# APP_UD_red_588.net
KiCad netlist of a schematic drawn in EAGLE
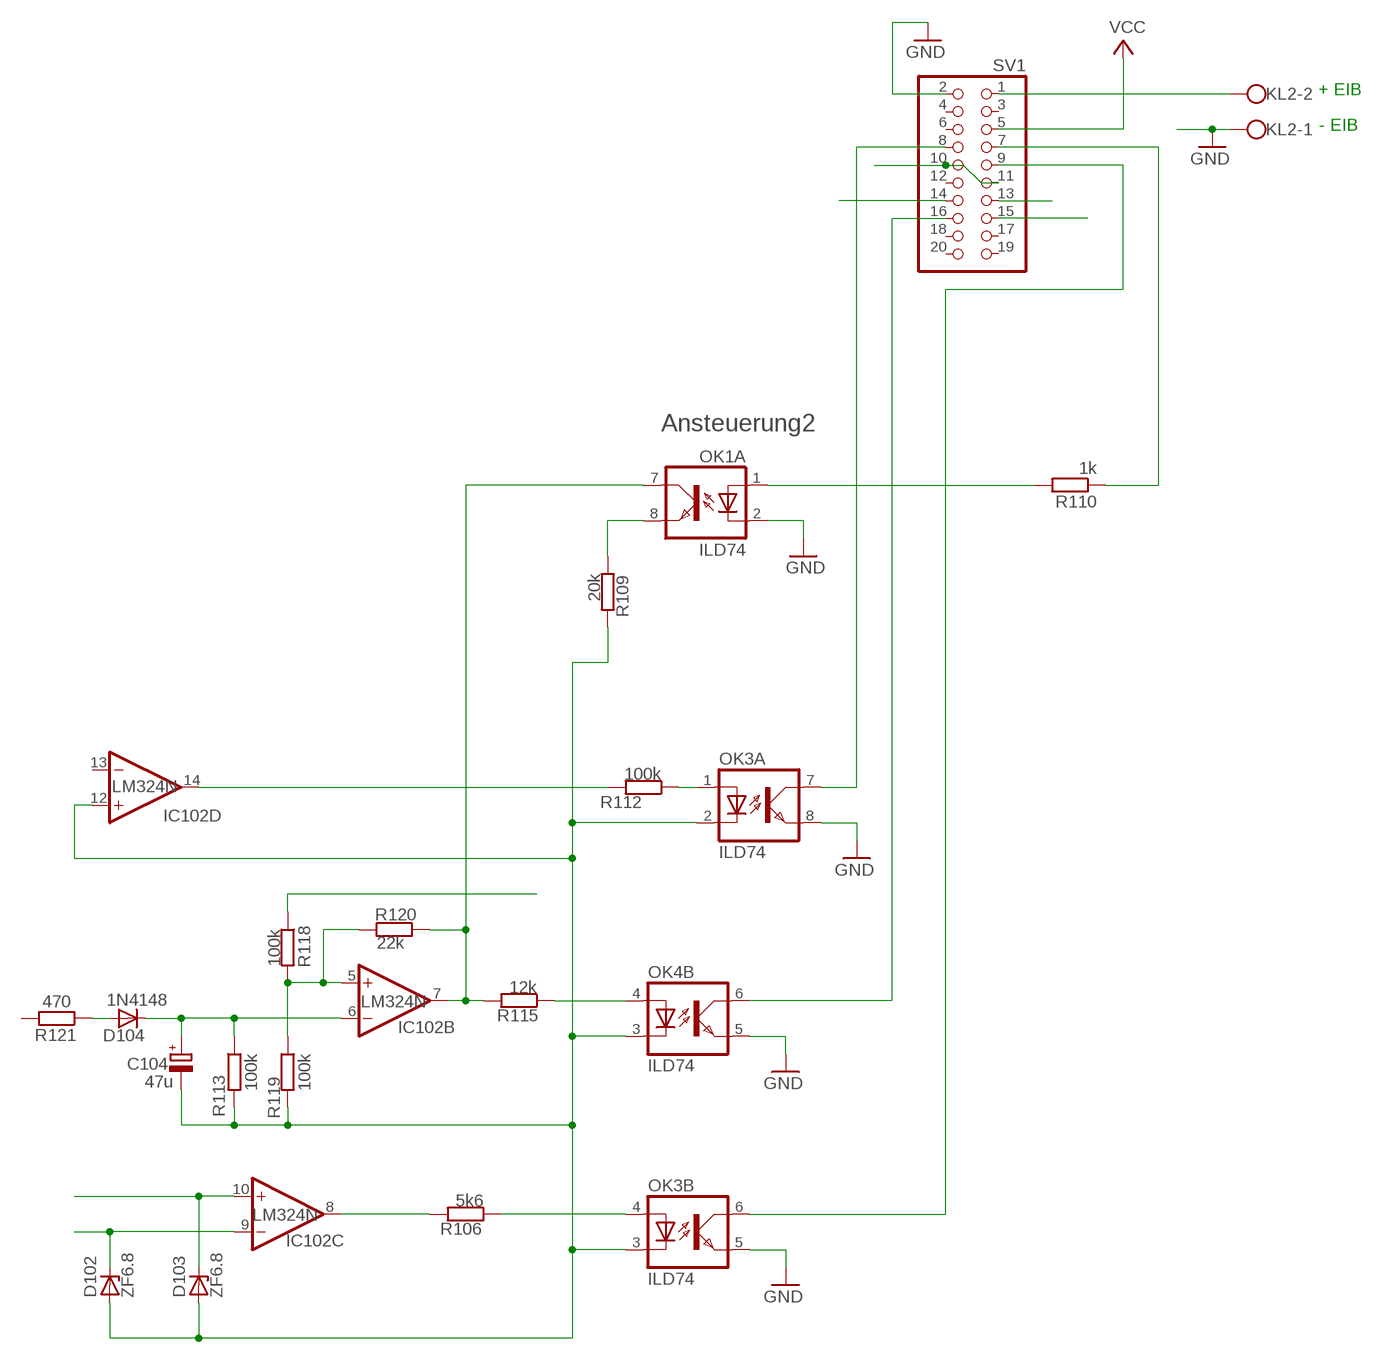
[diagram p0: schematic, sheet 1]

(export (version "E")
  (design (tool "Eeschema 10.0.6"))
  (components
    (comp (ref "C104")
      (value "47u")
      (footprint "eagle-import:E2-5")
      (libsource (lib "eagle-import") (part "CPOL-EUE2-5"))
    )
    (comp (ref "D102")
      (value "ZF6.8")
      (footprint "eagle-import:ZDIO-5")
      (libsource (lib "eagle-import") (part "ZENER-DIODEZD-5"))
    )
    (comp (ref "D103")
      (value "ZF6.8")
      (footprint "eagle-import:ZDIO-7.5")
      (libsource (lib "eagle-import") (part "ZENER-DIODEZD-7.5"))
    )
    (comp (ref "D104")
      (value "1N4148")
      (footprint "eagle-import:D-7")
      (libsource (lib "eagle-import") (part "1N4148DO35-7S"))
    )
    (comp (ref "IC102")
      (value "LM324N")
      (footprint "eagle-import:DIL14")
      (libsource (lib "eagle-import") (part "LM324N"))
    )
    (comp (ref "KL2")
      (value "W237-102")
      (footprint "eagle-import:W237-102")
      (libsource (lib "eagle-import") (part "W237-102"))
    )
    (comp (ref "OK1")
      (value "ILD74")
      (footprint "eagle-import:DIL08")
      (libsource (lib "eagle-import") (part "ILD2"))
    )
    (comp (ref "OK3")
      (value "ILD74")
      (footprint "eagle-import:DIL08")
      (libsource (lib "eagle-import") (part "ILD2"))
    )
    (comp (ref "OK4")
      (value "ILD74")
      (footprint "eagle-import:DIL08")
      (libsource (lib "eagle-import") (part "ILD2"))
    )
    (comp (ref "R106")
      (value "5k6")
      (footprint "eagle-import:0204_7")
      (libsource (lib "eagle-import") (part "R-EU_0204/7"))
    )
    (comp (ref "R109")
      (value "20k")
      (footprint "eagle-import:0204_7")
      (libsource (lib "eagle-import") (part "R-EU_0204/7"))
    )
    (comp (ref "R110")
      (value "1k")
      (footprint "eagle-import:0204_7")
      (libsource (lib "eagle-import") (part "R-EU_0204/7"))
    )
    (comp (ref "R112")
      (value "100k")
      (footprint "eagle-import:0207_15")
      (libsource (lib "eagle-import") (part "R-EU_0207/15"))
    )
    (comp (ref "R113")
      (value "100k")
      (footprint "eagle-import:0204_7")
      (libsource (lib "eagle-import") (part "R-EU_0204/7"))
    )
    (comp (ref "R115")
      (value "12k")
      (footprint "eagle-import:0204_7")
      (libsource (lib "eagle-import") (part "R-EU_0204/7"))
    )
    (comp (ref "R118")
      (value "100k")
      (footprint "eagle-import:0204_7")
      (libsource (lib "eagle-import") (part "R-EU_0204/7"))
    )
    (comp (ref "R119")
      (value "100k")
      (footprint "eagle-import:0204_7")
      (libsource (lib "eagle-import") (part "R-EU_0204/7"))
    )
    (comp (ref "R120")
      (value "22k")
      (footprint "eagle-import:0204_7")
      (libsource (lib "eagle-import") (part "R-EU_0204/7"))
    )
    (comp (ref "R121")
      (value "470")
      (footprint "eagle-import:0204_7")
      (libsource (lib "eagle-import") (part "R-EU_0204/7"))
    )
    (comp (ref "SV1")
      (value "PINHD-2X10")
      (footprint "eagle-import:2X10")
      (libsource (lib "eagle-import") (part "PINHD-2X10"))
    )
  )
  (nets
    (net (code "1") (name "GND") (class "Default")
      (node (ref "KL2") (pin "1") (pinfunction "KL_1") (pintype "passive"))
      (node (ref "OK1") (pin "2") (pinfunction "C_2") (pintype "passive"))
      (node (ref "OK3") (pin "5") (pinfunction "EMIT_5") (pintype "passive"))
      (node (ref "OK3") (pin "8") (pinfunction "EMIT_8") (pintype "passive"))
      (node (ref "OK4") (pin "5") (pinfunction "EMIT_5") (pintype "passive"))
      (node (ref "SV1") (pin "2") (pinfunction "2_2") (pintype "passive"))
    )
    (net (code "2") (name "Net-(D104-PadA)") (class "Default")
      (node (ref "D104") (pin "A") (pinfunction "A_A") (pintype "passive"))
      (node (ref "R121") (pin "1") (pinfunction "1_1") (pintype "passive"))
    )
    (net (code "3") (name "Net-(IC102B-+IN)") (class "Default")
      (node (ref "IC102") (pin "5") (pinfunction "+IN_5") (pintype "input"))
      (node (ref "R118") (pin "2") (pinfunction "2_2") (pintype "passive"))
      (node (ref "R119") (pin "1") (pinfunction "1_1") (pintype "passive"))
      (node (ref "R120") (pin "1") (pinfunction "1_1") (pintype "passive"))
    )
    (net (code "4") (name "Net-(IC102B--IN)") (class "Default")
      (node (ref "C104") (pin "+") (pinfunction "+_+") (pintype "passive"))
      (node (ref "D104") (pin "C") (pinfunction "C_C") (pintype "passive"))
      (node (ref "IC102") (pin "6") (pinfunction "-IN_6") (pintype "input"))
      (node (ref "R113") (pin "1") (pinfunction "1_1") (pintype "passive"))
    )
    (net (code "5") (name "Net-(IC102B-OUT)") (class "Default")
      (node (ref "IC102") (pin "7") (pinfunction "OUT_7") (pintype "output"))
      (node (ref "OK1") (pin "7") (pinfunction "COL_7") (pintype "passive"))
      (node (ref "R115") (pin "2") (pinfunction "2_2") (pintype "passive"))
      (node (ref "R120") (pin "2") (pinfunction "2_2") (pintype "passive"))
    )
    (net (code "6") (name "Net-(IC102C-+IN)") (class "Default")
      (node (ref "D103") (pin "C") (pinfunction "C_C") (pintype "passive"))
      (node (ref "IC102") (pin "10") (pinfunction "+IN_10") (pintype "input"))
    )
    (net (code "7") (name "Net-(IC102C--IN)") (class "Default")
      (node (ref "D102") (pin "C") (pinfunction "C_C") (pintype "passive"))
      (node (ref "IC102") (pin "9") (pinfunction "-IN_9") (pintype "input"))
    )
    (net (code "8") (name "Net-(IC102C-OUT)") (class "Default")
      (node (ref "IC102") (pin "8") (pinfunction "OUT_8") (pintype "output"))
      (node (ref "R106") (pin "2") (pinfunction "2_2") (pintype "passive"))
    )
    (net (code "9") (name "Net-(IC102D-+IN)") (class "Default")
      (node (ref "C104") (pin "-") (pinfunction "-_-") (pintype "passive"))
      (node (ref "D102") (pin "A") (pinfunction "A_A") (pintype "passive"))
      (node (ref "D103") (pin "A") (pinfunction "A_A") (pintype "passive"))
      (node (ref "IC102") (pin "12") (pinfunction "+IN_12") (pintype "input"))
      (node (ref "OK3") (pin "2") (pinfunction "C_2") (pintype "passive"))
      (node (ref "OK3") (pin "3") (pinfunction "C_3") (pintype "passive"))
      (node (ref "OK4") (pin "3") (pinfunction "C_3") (pintype "passive"))
      (node (ref "R109") (pin "2") (pinfunction "2_2") (pintype "passive"))
      (node (ref "R113") (pin "2") (pinfunction "2_2") (pintype "passive"))
      (node (ref "R119") (pin "2") (pinfunction "2_2") (pintype "passive"))
    )
    (net (code "10") (name "Net-(IC102D-OUT)") (class "Default")
      (node (ref "IC102") (pin "14") (pinfunction "OUT_14") (pintype "output"))
      (node (ref "R112") (pin "2") (pinfunction "2_2") (pintype "passive"))
    )
    (net (code "11") (name "Net-(KL2B-KL)") (class "Default")
      (node (ref "KL2") (pin "2") (pinfunction "KL_2") (pintype "passive"))
      (node (ref "SV1") (pin "1") (pinfunction "1_1") (pintype "passive"))
    )
    (net (code "12") (name "Net-(OK1A-A)") (class "Default")
      (node (ref "OK1") (pin "1") (pinfunction "A_1") (pintype "passive"))
      (node (ref "R110") (pin "2") (pinfunction "2_2") (pintype "passive"))
    )
    (net (code "13") (name "Net-(OK1A-EMIT)") (class "Default")
      (node (ref "OK1") (pin "8") (pinfunction "EMIT_8") (pintype "passive"))
      (node (ref "R109") (pin "1") (pinfunction "1_1") (pintype "passive"))
    )
    (net (code "14") (name "Net-(OK3A-A)") (class "Default")
      (node (ref "OK3") (pin "1") (pinfunction "A_1") (pintype "passive"))
      (node (ref "R112") (pin "1") (pinfunction "1_1") (pintype "passive"))
    )
    (net (code "15") (name "Net-(OK3A-COL)") (class "Default")
      (node (ref "OK3") (pin "7") (pinfunction "COL_7") (pintype "passive"))
      (node (ref "SV1") (pin "8") (pinfunction "8_8") (pintype "passive"))
    )
    (net (code "16") (name "Net-(OK3B-A)") (class "Default")
      (node (ref "OK3") (pin "4") (pinfunction "A_4") (pintype "passive"))
      (node (ref "R106") (pin "1") (pinfunction "1_1") (pintype "passive"))
    )
    (net (code "17") (name "Net-(OK3B-COL)") (class "Default")
      (node (ref "OK3") (pin "6") (pinfunction "COL_6") (pintype "passive"))
      (node (ref "SV1") (pin "9") (pinfunction "9_9") (pintype "passive"))
    )
    (net (code "18") (name "Net-(OK4B-A)") (class "Default")
      (node (ref "OK4") (pin "4") (pinfunction "A_4") (pintype "passive"))
      (node (ref "R115") (pin "1") (pinfunction "1_1") (pintype "passive"))
    )
    (net (code "19") (name "Net-(OK4B-COL)") (class "Default")
      (node (ref "OK4") (pin "6") (pinfunction "COL_6") (pintype "passive"))
      (node (ref "SV1") (pin "16") (pinfunction "16_16") (pintype "passive"))
    )
    (net (code "20") (name "Net-(R110-Pad1)") (class "Default")
      (node (ref "R110") (pin "1") (pinfunction "1_1") (pintype "passive"))
      (node (ref "SV1") (pin "7") (pinfunction "7_7") (pintype "passive"))
    )
    (net (code "21") (name "Net-(SV1-Pad10)") (class "Default")
      (node (ref "SV1") (pin "10") (pinfunction "10_10") (pintype "passive"))
      (node (ref "SV1") (pin "11") (pinfunction "11_11") (pintype "passive"))
    )
    (net (code "22") (name "VCC") (class "Default")
      (node (ref "SV1") (pin "5") (pinfunction "5_5") (pintype "passive"))
    )
    (net (code "23") (name "unconnected-(IC102D--IN-Pad13)") (class "Default")
      (node (ref "IC102") (pin "13") (pinfunction "-IN_13") (pintype "input"))
    )
    (net (code "24") (name "unconnected-(R118-Pad1)") (class "Default")
      (node (ref "R118") (pin "1") (pinfunction "1_1") (pintype "passive"))
    )
    (net (code "25") (name "unconnected-(R121-Pad2)") (class "Default")
      (node (ref "R121") (pin "2") (pinfunction "2_2") (pintype "passive"))
    )
    (net (code "26") (name "unconnected-(SV1-Pad3)") (class "Default")
      (node (ref "SV1") (pin "3") (pinfunction "3_3") (pintype "passive"))
    )
    (net (code "27") (name "unconnected-(SV1-Pad4)") (class "Default")
      (node (ref "SV1") (pin "4") (pinfunction "4_4") (pintype "passive"))
    )
    (net (code "28") (name "unconnected-(SV1-Pad6)") (class "Default")
      (node (ref "SV1") (pin "6") (pinfunction "6_6") (pintype "passive"))
    )
    (net (code "29") (name "unconnected-(SV1-Pad12)") (class "Default")
      (node (ref "SV1") (pin "12") (pinfunction "12_12") (pintype "passive"))
    )
    (net (code "30") (name "unconnected-(SV1-Pad13)") (class "Default")
      (node (ref "SV1") (pin "13") (pinfunction "13_13") (pintype "passive"))
    )
    (net (code "31") (name "unconnected-(SV1-Pad14)") (class "Default")
      (node (ref "SV1") (pin "14") (pinfunction "14_14") (pintype "passive"))
    )
    (net (code "32") (name "unconnected-(SV1-Pad15)") (class "Default")
      (node (ref "SV1") (pin "15") (pinfunction "15_15") (pintype "passive"))
    )
    (net (code "33") (name "unconnected-(SV1-Pad17)") (class "Default")
      (node (ref "SV1") (pin "17") (pinfunction "17_17") (pintype "passive"))
    )
    (net (code "34") (name "unconnected-(SV1-Pad18)") (class "Default")
      (node (ref "SV1") (pin "18") (pinfunction "18_18") (pintype "passive"))
    )
    (net (code "35") (name "unconnected-(SV1-Pad19)") (class "Default")
      (node (ref "SV1") (pin "19") (pinfunction "19_19") (pintype "passive"))
    )
    (net (code "36") (name "unconnected-(SV1-Pad20)") (class "Default")
      (node (ref "SV1") (pin "20") (pinfunction "20_20") (pintype "passive"))
    )
  )
)
